# power.net
KiCad netlist of a schematic drawn in EAGLE
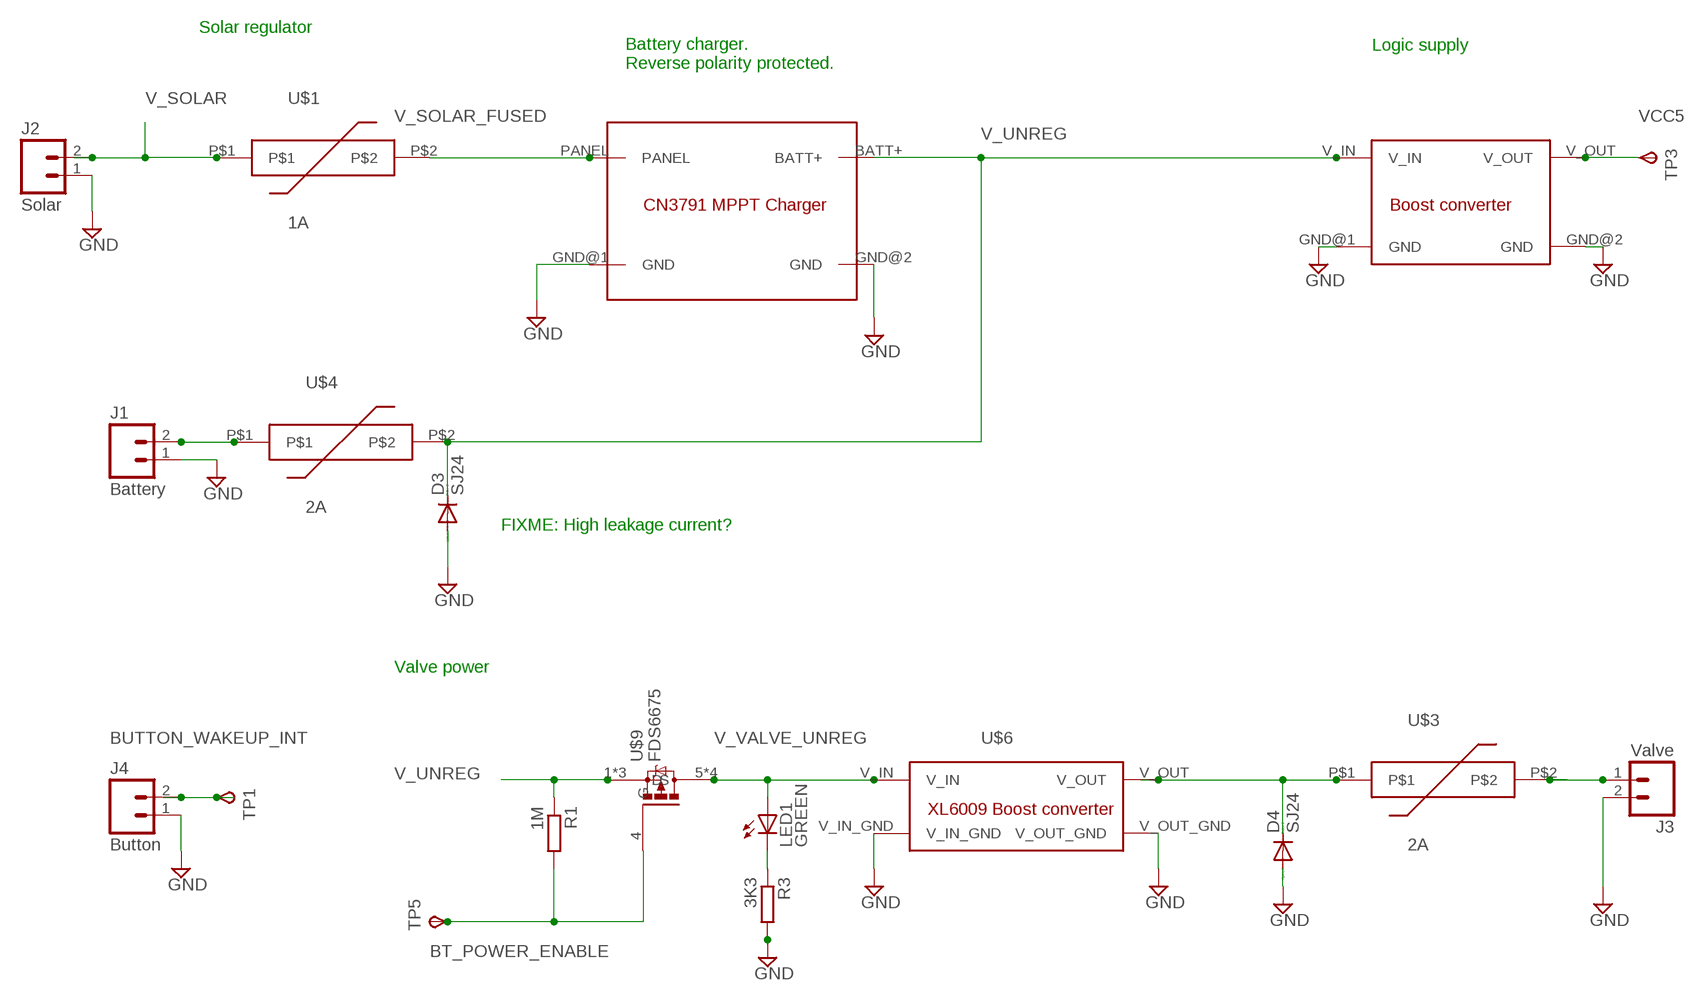
[diagram p0: schematic, sheet 1]

(export (version "E")
  (design (tool "Eeschema 10.0.6"))
  (components
    (comp (ref "D3")
      (value "SJ24")
      (footprint "eagle-import:SMB")
      (libsource (lib "eagle-import") (part "DIODE-SMB"))
    )
    (comp (ref "D4")
      (value "SJ24")
      (footprint "eagle-import:SMB")
      (libsource (lib "eagle-import") (part "DIODE-SMB"))
    )
    (comp (ref "J1")
      (value "Battery")
      (footprint "eagle-import:1X02_LONGPADS")
      (libsource (lib "eagle-import") (part "M02PTH3"))
    )
    (comp (ref "J2")
      (value "Solar")
      (footprint "eagle-import:1X02_LONGPADS")
      (libsource (lib "eagle-import") (part "M02PTH3"))
    )
    (comp (ref "J3")
      (value "Valve")
      (footprint "eagle-import:1X02_LONGPADS")
      (libsource (lib "eagle-import") (part "M02PTH3"))
    )
    (comp (ref "J4")
      (value "Button")
      (footprint "eagle-import:1X02_LONGPADS")
      (libsource (lib "eagle-import") (part "M02PTH3"))
    )
    (comp (ref "LED1")
      (value "GREEN")
      (footprint "eagle-import:LED3MM")
      (libsource (lib "eagle-import") (part "LED3MM"))
    )
    (comp (ref "R1")
      (value "1M")
      (footprint "eagle-import:R0805")
      (libsource (lib "eagle-import") (part "R-EU_R0805"))
    )
    (comp (ref "R3")
      (value "3K3")
      (footprint "eagle-import:R0805")
      (libsource (lib "eagle-import") (part "R-EU_R0805"))
    )
    (comp (ref "TP1")
      (value "TPSB1,27")
      (footprint "eagle-import:B1,27")
      (libsource (lib "eagle-import") (part "TPSB1,27"))
    )
    (comp (ref "TP3")
      (value "TPSB1,27")
      (footprint "eagle-import:B1,27")
      (libsource (lib "eagle-import") (part "TPSB1,27"))
    )
    (comp (ref "TP5")
      (value "TPSB1,27")
      (footprint "eagle-import:B1,27")
      (libsource (lib "eagle-import") (part "TPSB1,27"))
    )
    (comp (ref "U$1")
      (value "1A")
      (footprint "eagle-import:1812")
      (libsource (lib "eagle-import") (part "PTC"))
    )
    (comp (ref "U$2")
      (value "CN3791_MTTP_LIPO_SOLAR_CHARGER")
      (footprint "eagle-import:CN3791_MPPT_LIPO_SOLAR_CHARGER")
      (libsource (lib "eagle-import") (part "CN3791_MTTP_LIPO_SOLAR_CHARGER"))
    )
    (comp (ref "U$3")
      (value "2A")
      (footprint "eagle-import:1812")
      (libsource (lib "eagle-import") (part "PTC"))
    )
    (comp (ref "U$4")
      (value "2A")
      (footprint "eagle-import:1812")
      (libsource (lib "eagle-import") (part "PTC"))
    )
    (comp (ref "U$5")
      (value "QSKJ_BOOST_MODULE")
      (footprint "eagle-import:QSKJ_BOOST_MODULE")
      (libsource (lib "eagle-import") (part "QSKJ_BOOST_MODULE"))
    )
    (comp (ref "U$6")
      (value "XL6009_BOOST_MODULE")
      (footprint "eagle-import:XL6009_BOOST_MODULE")
      (libsource (lib "eagle-import") (part "XL6009_BOOST_MODULE"))
    )
    (comp (ref "U$9")
      (value "FDS6675")
      (footprint "eagle-import:SO08")
      (libsource (lib "eagle-import") (part "FDS6675"))
    )
  )
  (nets
    (net (code "1") (name "/BT_POWER_ENABLE") (class "Default")
      (node (ref "R1") (pin "2") (pinfunction "2_2") (pintype "passive"))
      (node (ref "TP5") (pin "TP") (pinfunction "PP_TP") (pintype "input"))
      (node (ref "U$9") (pin "4") (pinfunction "G_4") (pintype "bidirectional"))
    )
    (net (code "2") (name "/BUTTON_WAKEUP_INT") (class "Default")
      (node (ref "J4") (pin "2") (pinfunction "2_2") (pintype "passive"))
      (node (ref "TP1") (pin "TP") (pinfunction "PP_TP") (pintype "input"))
    )
    (net (code "3") (name "/VCC5") (class "Default")
      (node (ref "TP3") (pin "TP") (pinfunction "PP_TP") (pintype "input"))
      (node (ref "U$5") (pin "V_OUT") (pinfunction "V_OUT_V_OUT") (pintype "bidirectional"))
    )
    (net (code "4") (name "/V_SOLAR") (class "Default")
      (node (ref "J2") (pin "2") (pinfunction "2_2") (pintype "passive"))
      (node (ref "U$1") (pin "P$1") (pinfunction "P$1_P$1") (pintype "bidirectional"))
    )
    (net (code "5") (name "/V_SOLAR_FUSED") (class "Default")
      (node (ref "U$1") (pin "P$2") (pinfunction "P$2_P$2") (pintype "bidirectional"))
      (node (ref "U$2") (pin "PANEL") (pinfunction "PANEL_PANEL") (pintype "bidirectional"))
    )
    (net (code "6") (name "/V_UNREG") (class "Default")
      (node (ref "D3") (pin "C") (pinfunction "C_C") (pintype "passive"))
      (node (ref "R1") (pin "1") (pinfunction "1_1") (pintype "passive"))
      (node (ref "U$2") (pin "BATT+") (pinfunction "BATT+_BATT+") (pintype "bidirectional"))
      (node (ref "U$4") (pin "P$2") (pinfunction "P$2_P$2") (pintype "bidirectional"))
      (node (ref "U$5") (pin "V_IN") (pinfunction "V_IN_V_IN") (pintype "power_in"))
      (node (ref "U$9") (pin "1") (pinfunction "S_1") (pintype "bidirectional"))
      (node (ref "U$9") (pin "2") (pinfunction "S_2") (pintype "bidirectional"))
      (node (ref "U$9") (pin "3") (pinfunction "S_3") (pintype "bidirectional"))
    )
    (net (code "7") (name "/V_VALVE_UNREG") (class "Default")
      (node (ref "LED1") (pin "A") (pinfunction "A_A") (pintype "passive"))
      (node (ref "U$6") (pin "V_IN") (pinfunction "V_IN_V_IN") (pintype "power_in"))
      (node (ref "U$9") (pin "5") (pinfunction "D_5") (pintype "bidirectional"))
      (node (ref "U$9") (pin "6") (pinfunction "D_6") (pintype "bidirectional"))
      (node (ref "U$9") (pin "7") (pinfunction "D_7") (pintype "bidirectional"))
      (node (ref "U$9") (pin "8") (pinfunction "D_8") (pintype "bidirectional"))
    )
    (net (code "8") (name "GND") (class "Default")
      (node (ref "D3") (pin "A") (pinfunction "A_A") (pintype "passive"))
      (node (ref "D4") (pin "A") (pinfunction "A_A") (pintype "passive"))
      (node (ref "J1") (pin "1") (pinfunction "1_1") (pintype "passive"))
      (node (ref "J2") (pin "1") (pinfunction "1_1") (pintype "passive"))
      (node (ref "J3") (pin "2") (pinfunction "2_2") (pintype "passive"))
      (node (ref "J4") (pin "1") (pinfunction "1_1") (pintype "passive"))
      (node (ref "R3") (pin "2") (pinfunction "2_2") (pintype "passive"))
      (node (ref "U$2") (pin "GND@1") (pinfunction "GND_GND@1") (pintype "bidirectional"))
      (node (ref "U$2") (pin "GND@2") (pinfunction "GND_GND@2") (pintype "bidirectional"))
      (node (ref "U$5") (pin "GND@1") (pinfunction "GND_GND@1") (pintype "power_in"))
      (node (ref "U$5") (pin "GND@2") (pinfunction "GND_GND@2") (pintype "power_in"))
      (node (ref "U$6") (pin "V_IN_GND") (pinfunction "V_IN_GND_V_IN_GND") (pintype "power_in"))
      (node (ref "U$6") (pin "V_OUT_GND") (pinfunction "V_OUT_GND_V_OUT_GND") (pintype "power_in"))
    )
    (net (code "9") (name "Net-(D4-PadC)") (class "Default")
      (node (ref "D4") (pin "C") (pinfunction "C_C") (pintype "passive"))
      (node (ref "U$3") (pin "P$1") (pinfunction "P$1_P$1") (pintype "bidirectional"))
      (node (ref "U$6") (pin "V_OUT") (pinfunction "V_OUT_V_OUT") (pintype "output"))
    )
    (net (code "10") (name "Net-(J1-Pad2)") (class "Default")
      (node (ref "J1") (pin "2") (pinfunction "2_2") (pintype "passive"))
      (node (ref "U$4") (pin "P$1") (pinfunction "P$1_P$1") (pintype "bidirectional"))
    )
    (net (code "11") (name "Net-(J3-Pad1)") (class "Default")
      (node (ref "J3") (pin "1") (pinfunction "1_1") (pintype "passive"))
      (node (ref "U$3") (pin "P$2") (pinfunction "P$2_P$2") (pintype "bidirectional"))
    )
    (net (code "12") (name "Net-(LED1-C)") (class "Default")
      (node (ref "LED1") (pin "K") (pinfunction "C_K") (pintype "passive"))
      (node (ref "R3") (pin "1") (pinfunction "1_1") (pintype "passive"))
    )
  )
)
